# ws2812-hat.net
KiCad netlist of a schematic drawn in EAGLE
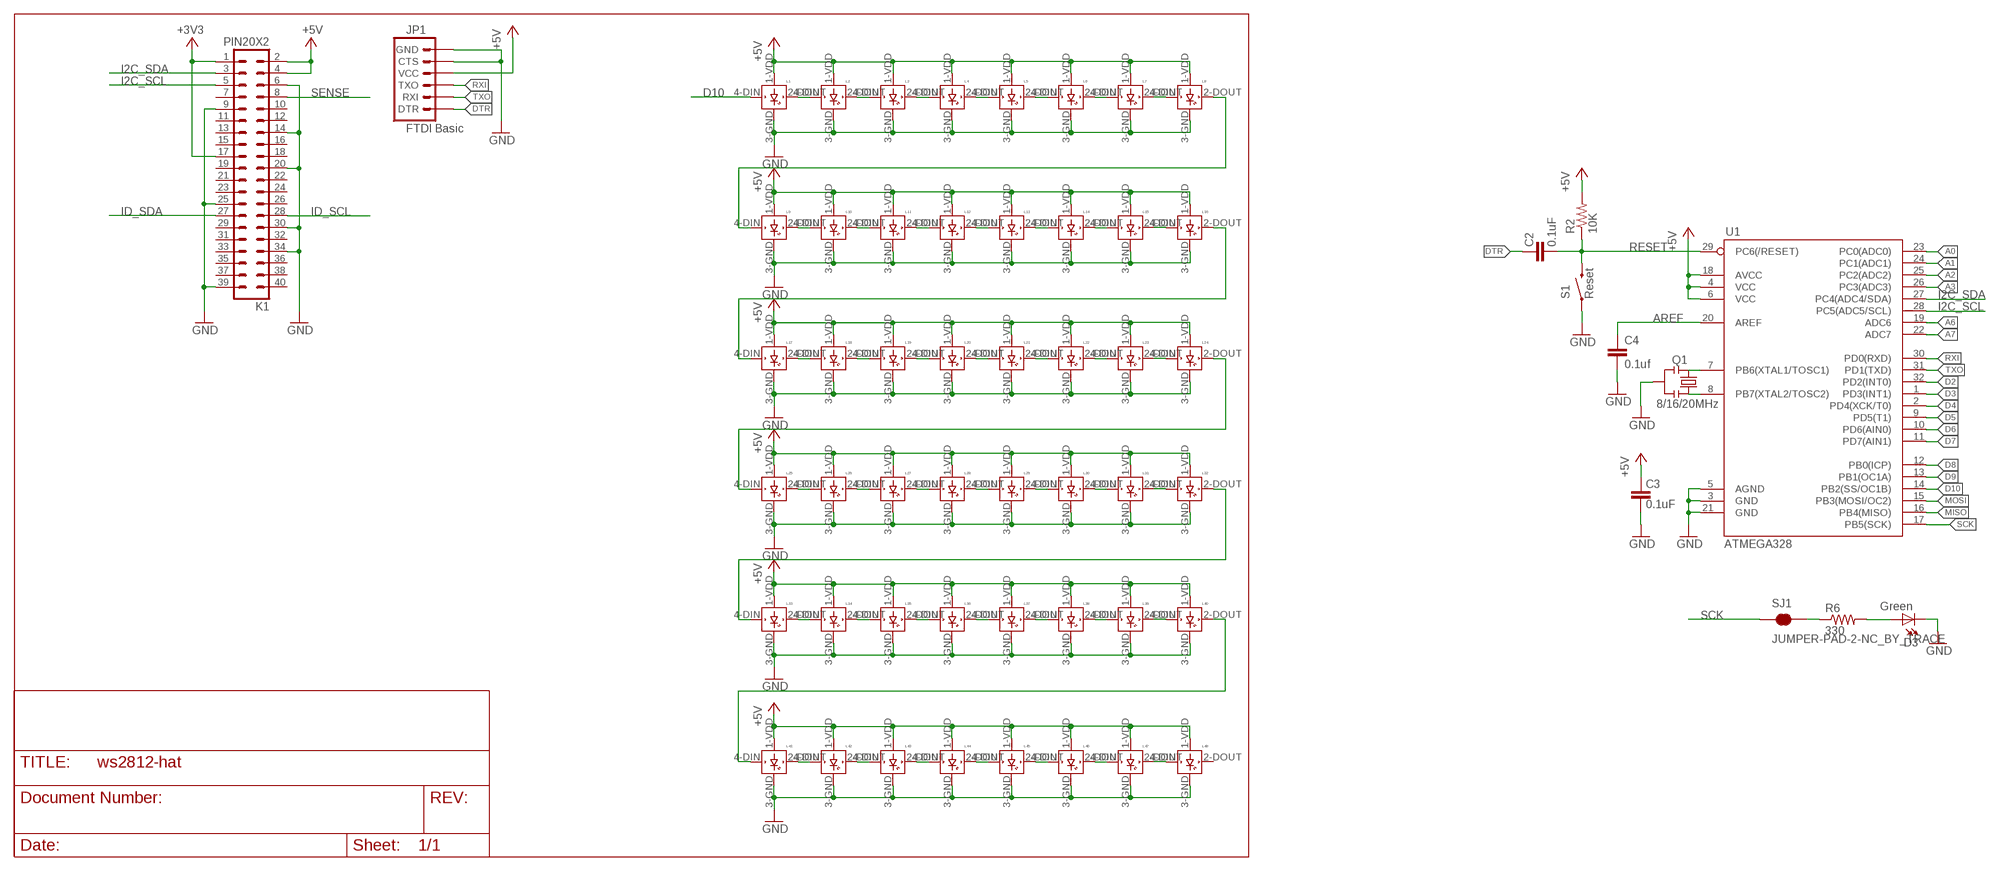
[diagram p0: schematic, sheet 1]

(export (version "E")
  (design (tool "Eeschema 10.0.6"))
  (components
    (comp (ref "C2")
      (value "0.1uF")
      (footprint "eagle-import:0603-CAP")
      (libsource (lib "eagle-import") (part "CAP0603-CAP"))
    )
    (comp (ref "C3")
      (value "0.1uF")
      (footprint "eagle-import:0603-CAP")
      (libsource (lib "eagle-import") (part "CAP0603-CAP"))
    )
    (comp (ref "C4")
      (value "0.1uf")
      (footprint "eagle-import:C0805K")
      (libsource (lib "eagle-import") (part "C-EUC0805K"))
    )
    (comp (ref "D3")
      (value "Green")
      (footprint "eagle-import:0603-LED-ALT1")
      (libsource (lib "eagle-import") (part "LED"))
    )
    (comp (ref "JP1")
      (value "FTDI Basic")
      (footprint "eagle-import:1X06")
      (libsource (lib "eagle-import") (part "ARDUINO_SERIAL_PROGRAMPTH"))
    )
    (comp (ref "K1")
      (value "PIN20X2")
      (footprint "eagle-import:PIN_20X2")
      (libsource (lib "eagle-import") (part "PIN20X2"))
    )
    (comp (ref "L1")
      (value "WS2812B")
      (footprint "eagle-import:WS2812B")
      (libsource (lib "eagle-import") (part "WS2812B"))
    )
    (comp (ref "L2")
      (value "WS2812B")
      (footprint "eagle-import:WS2812B")
      (libsource (lib "eagle-import") (part "WS2812B"))
    )
    (comp (ref "L3")
      (value "WS2812B")
      (footprint "eagle-import:WS2812B")
      (libsource (lib "eagle-import") (part "WS2812B"))
    )
    (comp (ref "L4")
      (value "WS2812B")
      (footprint "eagle-import:WS2812B")
      (libsource (lib "eagle-import") (part "WS2812B"))
    )
    (comp (ref "L5")
      (value "WS2812B")
      (footprint "eagle-import:WS2812B")
      (libsource (lib "eagle-import") (part "WS2812B"))
    )
    (comp (ref "L6")
      (value "WS2812B")
      (footprint "eagle-import:WS2812B")
      (libsource (lib "eagle-import") (part "WS2812B"))
    )
    (comp (ref "L7")
      (value "WS2812B")
      (footprint "eagle-import:WS2812B")
      (libsource (lib "eagle-import") (part "WS2812B"))
    )
    (comp (ref "L8")
      (value "WS2812B")
      (footprint "eagle-import:WS2812B")
      (libsource (lib "eagle-import") (part "WS2812B"))
    )
    (comp (ref "L9")
      (value "WS2812B")
      (footprint "eagle-import:WS2812B")
      (libsource (lib "eagle-import") (part "WS2812B"))
    )
    (comp (ref "L10")
      (value "WS2812B")
      (footprint "eagle-import:WS2812B")
      (libsource (lib "eagle-import") (part "WS2812B"))
    )
    (comp (ref "L11")
      (value "WS2812B")
      (footprint "eagle-import:WS2812B")
      (libsource (lib "eagle-import") (part "WS2812B"))
    )
    (comp (ref "L12")
      (value "WS2812B")
      (footprint "eagle-import:WS2812B")
      (libsource (lib "eagle-import") (part "WS2812B"))
    )
    (comp (ref "L13")
      (value "WS2812B")
      (footprint "eagle-import:WS2812B")
      (libsource (lib "eagle-import") (part "WS2812B"))
    )
    (comp (ref "L14")
      (value "WS2812B")
      (footprint "eagle-import:WS2812B")
      (libsource (lib "eagle-import") (part "WS2812B"))
    )
    (comp (ref "L15")
      (value "WS2812B")
      (footprint "eagle-import:WS2812B")
      (libsource (lib "eagle-import") (part "WS2812B"))
    )
    (comp (ref "L16")
      (value "WS2812B")
      (footprint "eagle-import:WS2812B")
      (libsource (lib "eagle-import") (part "WS2812B"))
    )
    (comp (ref "L17")
      (value "WS2812B")
      (footprint "eagle-import:WS2812B")
      (libsource (lib "eagle-import") (part "WS2812B"))
    )
    (comp (ref "L18")
      (value "WS2812B")
      (footprint "eagle-import:WS2812B")
      (libsource (lib "eagle-import") (part "WS2812B"))
    )
    (comp (ref "L19")
      (value "WS2812B")
      (footprint "eagle-import:WS2812B")
      (libsource (lib "eagle-import") (part "WS2812B"))
    )
    (comp (ref "L20")
      (value "WS2812B")
      (footprint "eagle-import:WS2812B")
      (libsource (lib "eagle-import") (part "WS2812B"))
    )
    (comp (ref "L21")
      (value "WS2812B")
      (footprint "eagle-import:WS2812B")
      (libsource (lib "eagle-import") (part "WS2812B"))
    )
    (comp (ref "L22")
      (value "WS2812B")
      (footprint "eagle-import:WS2812B")
      (libsource (lib "eagle-import") (part "WS2812B"))
    )
    (comp (ref "L23")
      (value "WS2812B")
      (footprint "eagle-import:WS2812B")
      (libsource (lib "eagle-import") (part "WS2812B"))
    )
    (comp (ref "L24")
      (value "WS2812B")
      (footprint "eagle-import:WS2812B")
      (libsource (lib "eagle-import") (part "WS2812B"))
    )
    (comp (ref "L25")
      (value "WS2812B")
      (footprint "eagle-import:WS2812B")
      (libsource (lib "eagle-import") (part "WS2812B"))
    )
    (comp (ref "L26")
      (value "WS2812B")
      (footprint "eagle-import:WS2812B")
      (libsource (lib "eagle-import") (part "WS2812B"))
    )
    (comp (ref "L27")
      (value "WS2812B")
      (footprint "eagle-import:WS2812B")
      (libsource (lib "eagle-import") (part "WS2812B"))
    )
    (comp (ref "L28")
      (value "WS2812B")
      (footprint "eagle-import:WS2812B")
      (libsource (lib "eagle-import") (part "WS2812B"))
    )
    (comp (ref "L29")
      (value "WS2812B")
      (footprint "eagle-import:WS2812B")
      (libsource (lib "eagle-import") (part "WS2812B"))
    )
    (comp (ref "L30")
      (value "WS2812B")
      (footprint "eagle-import:WS2812B")
      (libsource (lib "eagle-import") (part "WS2812B"))
    )
    (comp (ref "L31")
      (value "WS2812B")
      (footprint "eagle-import:WS2812B")
      (libsource (lib "eagle-import") (part "WS2812B"))
    )
    (comp (ref "L32")
      (value "WS2812B")
      (footprint "eagle-import:WS2812B")
      (libsource (lib "eagle-import") (part "WS2812B"))
    )
    (comp (ref "L33")
      (value "WS2812B")
      (footprint "eagle-import:WS2812B")
      (libsource (lib "eagle-import") (part "WS2812B"))
    )
    (comp (ref "L34")
      (value "WS2812B")
      (footprint "eagle-import:WS2812B")
      (libsource (lib "eagle-import") (part "WS2812B"))
    )
    (comp (ref "L35")
      (value "WS2812B")
      (footprint "eagle-import:WS2812B")
      (libsource (lib "eagle-import") (part "WS2812B"))
    )
    (comp (ref "L36")
      (value "WS2812B")
      (footprint "eagle-import:WS2812B")
      (libsource (lib "eagle-import") (part "WS2812B"))
    )
    (comp (ref "L37")
      (value "WS2812B")
      (footprint "eagle-import:WS2812B")
      (libsource (lib "eagle-import") (part "WS2812B"))
    )
    (comp (ref "L38")
      (value "WS2812B")
      (footprint "eagle-import:WS2812B")
      (libsource (lib "eagle-import") (part "WS2812B"))
    )
    (comp (ref "L39")
      (value "WS2812B")
      (footprint "eagle-import:WS2812B")
      (libsource (lib "eagle-import") (part "WS2812B"))
    )
    (comp (ref "L40")
      (value "WS2812B")
      (footprint "eagle-import:WS2812B")
      (libsource (lib "eagle-import") (part "WS2812B"))
    )
    (comp (ref "L41")
      (value "WS2812B")
      (footprint "eagle-import:WS2812B")
      (libsource (lib "eagle-import") (part "WS2812B"))
    )
    (comp (ref "L42")
      (value "WS2812B")
      (footprint "eagle-import:WS2812B")
      (libsource (lib "eagle-import") (part "WS2812B"))
    )
    (comp (ref "L43")
      (value "WS2812B")
      (footprint "eagle-import:WS2812B")
      (libsource (lib "eagle-import") (part "WS2812B"))
    )
    (comp (ref "L44")
      (value "WS2812B")
      (footprint "eagle-import:WS2812B")
      (libsource (lib "eagle-import") (part "WS2812B"))
    )
    (comp (ref "L45")
      (value "WS2812B")
      (footprint "eagle-import:WS2812B")
      (libsource (lib "eagle-import") (part "WS2812B"))
    )
    (comp (ref "L46")
      (value "WS2812B")
      (footprint "eagle-import:WS2812B")
      (libsource (lib "eagle-import") (part "WS2812B"))
    )
    (comp (ref "L47")
      (value "WS2812B")
      (footprint "eagle-import:WS2812B")
      (libsource (lib "eagle-import") (part "WS2812B"))
    )
    (comp (ref "L48")
      (value "WS2812B")
      (footprint "eagle-import:WS2812B")
      (libsource (lib "eagle-import") (part "WS2812B"))
    )
    (comp (ref "Q1")
      (value "8/16/20MHz")
      (footprint "eagle-import:RESONATOR-SMD-1_1")
      (libsource (lib "eagle-import") (part "RESONATOR1{colon}1"))
    )
    (comp (ref "R2")
      (value "10K")
      (footprint "eagle-import:0603-RES")
      (libsource (lib "eagle-import") (part "RESISTOR0603-RES"))
    )
    (comp (ref "R6")
      (value "330")
      (footprint "eagle-import:0603-RES")
      (libsource (lib "eagle-import") (part "RESISTOR0603-RES"))
    )
    (comp (ref "S1")
      (value "Reset")
      (footprint "eagle-import:TACTILE-SWITCH-SMD-ALT01")
      (libsource (lib "eagle-import") (part "SWITCH-MOMENTARY-2SMD-ALT01"))
    )
    (comp (ref "SJ1")
      (value "JUMPER-PAD-2-NC_BY_TRACE")
      (footprint "eagle-import:PAD-JUMPER-2-NC_BY_TRACE_YES_SILK")
      (libsource (lib "eagle-import") (part "JUMPER-PAD-2-NC_BY_TRACE"))
    )
    (comp (ref "U1")
      (value "ATMEGA328")
      (footprint "eagle-import:TQFP32-08")
      (libsource (lib "eagle-import") (part "ATMEGA168"))
    )
  )
  (nets
    (net (code "1") (name "+3V3") (class "Default")
      (node (ref "K1") (pin "1") (pinfunction "1_1") (pintype "passive"))
      (node (ref "K1") (pin "17") (pinfunction "17_17") (pintype "passive"))
    )
    (net (code "2") (name "+5V") (class "Default")
      (node (ref "C3") (pin "2") (pinfunction "2_2") (pintype "passive"))
      (node (ref "JP1") (pin "4") (pinfunction "VCC_4") (pintype "passive"))
      (node (ref "K1") (pin "2") (pinfunction "2_2") (pintype "passive"))
      (node (ref "K1") (pin "4") (pinfunction "4_4") (pintype "passive"))
      (node (ref "L1") (pin "1-VDD") (pinfunction "VDD_1-VDD") (pintype "bidirectional"))
      (node (ref "L10") (pin "1-VDD") (pinfunction "VDD_1-VDD") (pintype "bidirectional"))
      (node (ref "L11") (pin "1-VDD") (pinfunction "VDD_1-VDD") (pintype "bidirectional"))
      (node (ref "L12") (pin "1-VDD") (pinfunction "VDD_1-VDD") (pintype "bidirectional"))
      (node (ref "L13") (pin "1-VDD") (pinfunction "VDD_1-VDD") (pintype "bidirectional"))
      (node (ref "L14") (pin "1-VDD") (pinfunction "VDD_1-VDD") (pintype "bidirectional"))
      (node (ref "L15") (pin "1-VDD") (pinfunction "VDD_1-VDD") (pintype "bidirectional"))
      (node (ref "L16") (pin "1-VDD") (pinfunction "VDD_1-VDD") (pintype "bidirectional"))
      (node (ref "L17") (pin "1-VDD") (pinfunction "VDD_1-VDD") (pintype "bidirectional"))
      (node (ref "L18") (pin "1-VDD") (pinfunction "VDD_1-VDD") (pintype "bidirectional"))
      (node (ref "L19") (pin "1-VDD") (pinfunction "VDD_1-VDD") (pintype "bidirectional"))
      (node (ref "L2") (pin "1-VDD") (pinfunction "VDD_1-VDD") (pintype "bidirectional"))
      (node (ref "L20") (pin "1-VDD") (pinfunction "VDD_1-VDD") (pintype "bidirectional"))
      (node (ref "L21") (pin "1-VDD") (pinfunction "VDD_1-VDD") (pintype "bidirectional"))
      (node (ref "L22") (pin "1-VDD") (pinfunction "VDD_1-VDD") (pintype "bidirectional"))
      (node (ref "L23") (pin "1-VDD") (pinfunction "VDD_1-VDD") (pintype "bidirectional"))
      (node (ref "L24") (pin "1-VDD") (pinfunction "VDD_1-VDD") (pintype "bidirectional"))
      (node (ref "L25") (pin "1-VDD") (pinfunction "VDD_1-VDD") (pintype "bidirectional"))
      (node (ref "L26") (pin "1-VDD") (pinfunction "VDD_1-VDD") (pintype "bidirectional"))
      (node (ref "L27") (pin "1-VDD") (pinfunction "VDD_1-VDD") (pintype "bidirectional"))
      (node (ref "L28") (pin "1-VDD") (pinfunction "VDD_1-VDD") (pintype "bidirectional"))
      (node (ref "L29") (pin "1-VDD") (pinfunction "VDD_1-VDD") (pintype "bidirectional"))
      (node (ref "L3") (pin "1-VDD") (pinfunction "VDD_1-VDD") (pintype "bidirectional"))
      (node (ref "L30") (pin "1-VDD") (pinfunction "VDD_1-VDD") (pintype "bidirectional"))
      (node (ref "L31") (pin "1-VDD") (pinfunction "VDD_1-VDD") (pintype "bidirectional"))
      (node (ref "L32") (pin "1-VDD") (pinfunction "VDD_1-VDD") (pintype "bidirectional"))
      (node (ref "L33") (pin "1-VDD") (pinfunction "VDD_1-VDD") (pintype "bidirectional"))
      (node (ref "L34") (pin "1-VDD") (pinfunction "VDD_1-VDD") (pintype "bidirectional"))
      (node (ref "L35") (pin "1-VDD") (pinfunction "VDD_1-VDD") (pintype "bidirectional"))
      (node (ref "L36") (pin "1-VDD") (pinfunction "VDD_1-VDD") (pintype "bidirectional"))
      (node (ref "L37") (pin "1-VDD") (pinfunction "VDD_1-VDD") (pintype "bidirectional"))
      (node (ref "L38") (pin "1-VDD") (pinfunction "VDD_1-VDD") (pintype "bidirectional"))
      (node (ref "L39") (pin "1-VDD") (pinfunction "VDD_1-VDD") (pintype "bidirectional"))
      (node (ref "L4") (pin "1-VDD") (pinfunction "VDD_1-VDD") (pintype "bidirectional"))
      (node (ref "L40") (pin "1-VDD") (pinfunction "VDD_1-VDD") (pintype "bidirectional"))
      (node (ref "L41") (pin "1-VDD") (pinfunction "VDD_1-VDD") (pintype "bidirectional"))
      (node (ref "L42") (pin "1-VDD") (pinfunction "VDD_1-VDD") (pintype "bidirectional"))
      (node (ref "L43") (pin "1-VDD") (pinfunction "VDD_1-VDD") (pintype "bidirectional"))
      (node (ref "L44") (pin "1-VDD") (pinfunction "VDD_1-VDD") (pintype "bidirectional"))
      (node (ref "L45") (pin "1-VDD") (pinfunction "VDD_1-VDD") (pintype "bidirectional"))
      (node (ref "L46") (pin "1-VDD") (pinfunction "VDD_1-VDD") (pintype "bidirectional"))
      (node (ref "L47") (pin "1-VDD") (pinfunction "VDD_1-VDD") (pintype "bidirectional"))
      (node (ref "L48") (pin "1-VDD") (pinfunction "VDD_1-VDD") (pintype "bidirectional"))
      (node (ref "L5") (pin "1-VDD") (pinfunction "VDD_1-VDD") (pintype "bidirectional"))
      (node (ref "L6") (pin "1-VDD") (pinfunction "VDD_1-VDD") (pintype "bidirectional"))
      (node (ref "L7") (pin "1-VDD") (pinfunction "VDD_1-VDD") (pintype "bidirectional"))
      (node (ref "L8") (pin "1-VDD") (pinfunction "VDD_1-VDD") (pintype "bidirectional"))
      (node (ref "L9") (pin "1-VDD") (pinfunction "VDD_1-VDD") (pintype "bidirectional"))
      (node (ref "R2") (pin "2") (pinfunction "2_2") (pintype "passive"))
      (node (ref "U1") (pin "18") (pinfunction "AVCC_18") (pintype "bidirectional"))
      (node (ref "U1") (pin "4") (pinfunction "VCC_4") (pintype "bidirectional"))
      (node (ref "U1") (pin "6") (pinfunction "VCC_6") (pintype "bidirectional"))
    )
    (net (code "3") (name "/AREF") (class "Default")
      (node (ref "C4") (pin "1") (pinfunction "1_1") (pintype "passive"))
      (node (ref "U1") (pin "20") (pinfunction "AREF_20") (pintype "bidirectional"))
    )
    (net (code "4") (name "/I2C_SCL") (class "Default")
      (node (ref "K1") (pin "5") (pinfunction "5_5") (pintype "passive"))
      (node (ref "U1") (pin "28") (pinfunction "PC5(ADC5/SCL)_28") (pintype "bidirectional"))
    )
    (net (code "5") (name "/I2C_SDA") (class "Default")
      (node (ref "K1") (pin "3") (pinfunction "3_3") (pintype "passive"))
      (node (ref "U1") (pin "27") (pinfunction "PC4(ADC4/SDA)_27") (pintype "bidirectional"))
    )
    (net (code "6") (name "/ID_SCL") (class "Default")
      (node (ref "K1") (pin "28") (pinfunction "28_28") (pintype "passive"))
    )
    (net (code "7") (name "/ID_SDA") (class "Default")
      (node (ref "K1") (pin "27") (pinfunction "27_27") (pintype "passive"))
    )
    (net (code "8") (name "/RESET") (class "Default")
      (node (ref "C2") (pin "1") (pinfunction "1_1") (pintype "passive"))
      (node (ref "R2") (pin "1") (pinfunction "1_1") (pintype "passive"))
      (node (ref "S1") (pin "3") (pinfunction "2_3") (pintype "passive"))
      (node (ref "S1") (pin "4") (pinfunction "2_4") (pintype "passive"))
      (node (ref "U1") (pin "29") (pinfunction "PC6(/RESET)_29") (pintype "bidirectional"))
    )
    (net (code "9") (name "/SENSE") (class "Default")
      (node (ref "K1") (pin "8") (pinfunction "8_8") (pintype "passive"))
    )
    (net (code "10") (name "A0") (class "Default")
      (node (ref "U1") (pin "23") (pinfunction "PC0(ADC0)_23") (pintype "bidirectional"))
    )
    (net (code "11") (name "A1") (class "Default")
      (node (ref "U1") (pin "24") (pinfunction "PC1(ADC1)_24") (pintype "bidirectional"))
    )
    (net (code "12") (name "A2") (class "Default")
      (node (ref "U1") (pin "25") (pinfunction "PC2(ADC2)_25") (pintype "bidirectional"))
    )
    (net (code "13") (name "A3") (class "Default")
      (node (ref "U1") (pin "26") (pinfunction "PC3(ADC3)_26") (pintype "bidirectional"))
    )
    (net (code "14") (name "A6") (class "Default")
      (node (ref "U1") (pin "19") (pinfunction "ADC6_19") (pintype "bidirectional"))
    )
    (net (code "15") (name "A7") (class "Default")
      (node (ref "U1") (pin "22") (pinfunction "ADC7_22") (pintype "bidirectional"))
    )
    (net (code "16") (name "D2") (class "Default")
      (node (ref "U1") (pin "32") (pinfunction "PD2(INT0)_32") (pintype "bidirectional"))
    )
    (net (code "17") (name "D3") (class "Default")
      (node (ref "U1") (pin "1") (pinfunction "PD3(INT1)_1") (pintype "bidirectional"))
    )
    (net (code "18") (name "D4") (class "Default")
      (node (ref "U1") (pin "2") (pinfunction "PD4(XCK/T0)_2") (pintype "bidirectional"))
    )
    (net (code "19") (name "D5") (class "Default")
      (node (ref "U1") (pin "9") (pinfunction "PD5(T1)_9") (pintype "bidirectional"))
    )
    (net (code "20") (name "D6") (class "Default")
      (node (ref "U1") (pin "10") (pinfunction "PD6(AIN0)_10") (pintype "bidirectional"))
    )
    (net (code "21") (name "D7") (class "Default")
      (node (ref "U1") (pin "11") (pinfunction "PD7(AIN1)_11") (pintype "bidirectional"))
    )
    (net (code "22") (name "D8") (class "Default")
      (node (ref "U1") (pin "12") (pinfunction "PB0(ICP)_12") (pintype "bidirectional"))
    )
    (net (code "23") (name "D9") (class "Default")
      (node (ref "U1") (pin "13") (pinfunction "PB1(OC1A)_13") (pintype "bidirectional"))
    )
    (net (code "24") (name "D10") (class "Default")
      (node (ref "L1") (pin "4-DIN") (pinfunction "DIN_4-DIN") (pintype "input"))
      (node (ref "U1") (pin "14") (pinfunction "PB2(SS/OC1B)_14") (pintype "bidirectional"))
    )
    (net (code "25") (name "DTR") (class "Default")
      (node (ref "C2") (pin "2") (pinfunction "2_2") (pintype "passive"))
      (node (ref "JP1") (pin "1") (pinfunction "DTR_1") (pintype "passive"))
    )
    (net (code "26") (name "GND") (class "Default")
      (node (ref "C3") (pin "1") (pinfunction "1_1") (pintype "passive"))
      (node (ref "C4") (pin "2") (pinfunction "2_2") (pintype "passive"))
      (node (ref "D3") (pin "C") (pinfunction "C_C") (pintype "passive"))
      (node (ref "JP1") (pin "5") (pinfunction "CTS_5") (pintype "passive"))
      (node (ref "JP1") (pin "6") (pinfunction "GND_6") (pintype "passive"))
      (node (ref "K1") (pin "14") (pinfunction "14_14") (pintype "passive"))
      (node (ref "K1") (pin "20") (pinfunction "20_20") (pintype "passive"))
      (node (ref "K1") (pin "25") (pinfunction "25_25") (pintype "passive"))
      (node (ref "K1") (pin "30") (pinfunction "30_30") (pintype "passive"))
      (node (ref "K1") (pin "34") (pinfunction "34_34") (pintype "passive"))
      (node (ref "K1") (pin "39") (pinfunction "39_39") (pintype "passive"))
      (node (ref "K1") (pin "6") (pinfunction "6_6") (pintype "passive"))
      (node (ref "K1") (pin "9") (pinfunction "9_9") (pintype "passive"))
      (node (ref "L1") (pin "3-GND") (pinfunction "GND_3-GND") (pintype "bidirectional"))
      (node (ref "L10") (pin "3-GND") (pinfunction "GND_3-GND") (pintype "bidirectional"))
      (node (ref "L11") (pin "3-GND") (pinfunction "GND_3-GND") (pintype "bidirectional"))
      (node (ref "L12") (pin "3-GND") (pinfunction "GND_3-GND") (pintype "bidirectional"))
      (node (ref "L13") (pin "3-GND") (pinfunction "GND_3-GND") (pintype "bidirectional"))
      (node (ref "L14") (pin "3-GND") (pinfunction "GND_3-GND") (pintype "bidirectional"))
      (node (ref "L15") (pin "3-GND") (pinfunction "GND_3-GND") (pintype "bidirectional"))
      (node (ref "L16") (pin "3-GND") (pinfunction "GND_3-GND") (pintype "bidirectional"))
      (node (ref "L17") (pin "3-GND") (pinfunction "GND_3-GND") (pintype "bidirectional"))
      (node (ref "L18") (pin "3-GND") (pinfunction "GND_3-GND") (pintype "bidirectional"))
      (node (ref "L19") (pin "3-GND") (pinfunction "GND_3-GND") (pintype "bidirectional"))
      (node (ref "L2") (pin "3-GND") (pinfunction "GND_3-GND") (pintype "bidirectional"))
      (node (ref "L20") (pin "3-GND") (pinfunction "GND_3-GND") (pintype "bidirectional"))
      (node (ref "L21") (pin "3-GND") (pinfunction "GND_3-GND") (pintype "bidirectional"))
      (node (ref "L22") (pin "3-GND") (pinfunction "GND_3-GND") (pintype "bidirectional"))
      (node (ref "L23") (pin "3-GND") (pinfunction "GND_3-GND") (pintype "bidirectional"))
      (node (ref "L24") (pin "3-GND") (pinfunction "GND_3-GND") (pintype "bidirectional"))
      (node (ref "L25") (pin "3-GND") (pinfunction "GND_3-GND") (pintype "bidirectional"))
      (node (ref "L26") (pin "3-GND") (pinfunction "GND_3-GND") (pintype "bidirectional"))
      (node (ref "L27") (pin "3-GND") (pinfunction "GND_3-GND") (pintype "bidirectional"))
      (node (ref "L28") (pin "3-GND") (pinfunction "GND_3-GND") (pintype "bidirectional"))
      (node (ref "L29") (pin "3-GND") (pinfunction "GND_3-GND") (pintype "bidirectional"))
      (node (ref "L3") (pin "3-GND") (pinfunction "GND_3-GND") (pintype "bidirectional"))
      (node (ref "L30") (pin "3-GND") (pinfunction "GND_3-GND") (pintype "bidirectional"))
      (node (ref "L31") (pin "3-GND") (pinfunction "GND_3-GND") (pintype "bidirectional"))
      (node (ref "L32") (pin "3-GND") (pinfunction "GND_3-GND") (pintype "bidirectional"))
      (node (ref "L33") (pin "3-GND") (pinfunction "GND_3-GND") (pintype "bidirectional"))
      (node (ref "L34") (pin "3-GND") (pinfunction "GND_3-GND") (pintype "bidirectional"))
      (node (ref "L35") (pin "3-GND") (pinfunction "GND_3-GND") (pintype "bidirectional"))
      (node (ref "L36") (pin "3-GND") (pinfunction "GND_3-GND") (pintype "bidirectional"))
      (node (ref "L37") (pin "3-GND") (pinfunction "GND_3-GND") (pintype "bidirectional"))
      (node (ref "L38") (pin "3-GND") (pinfunction "GND_3-GND") (pintype "bidirectional"))
      (node (ref "L39") (pin "3-GND") (pinfunction "GND_3-GND") (pintype "bidirectional"))
      (node (ref "L4") (pin "3-GND") (pinfunction "GND_3-GND") (pintype "bidirectional"))
      (node (ref "L40") (pin "3-GND") (pinfunction "GND_3-GND") (pintype "bidirectional"))
      (node (ref "L41") (pin "3-GND") (pinfunction "GND_3-GND") (pintype "bidirectional"))
      (node (ref "L42") (pin "3-GND") (pinfunction "GND_3-GND") (pintype "bidirectional"))
      (node (ref "L43") (pin "3-GND") (pinfunction "GND_3-GND") (pintype "bidirectional"))
      (node (ref "L44") (pin "3-GND") (pinfunction "GND_3-GND") (pintype "bidirectional"))
      (node (ref "L45") (pin "3-GND") (pinfunction "GND_3-GND") (pintype "bidirectional"))
      (node (ref "L46") (pin "3-GND") (pinfunction "GND_3-GND") (pintype "bidirectional"))
      (node (ref "L47") (pin "3-GND") (pinfunction "GND_3-GND") (pintype "bidirectional"))
      (node (ref "L48") (pin "3-GND") (pinfunction "GND_3-GND") (pintype "bidirectional"))
      (node (ref "L5") (pin "3-GND") (pinfunction "GND_3-GND") (pintype "bidirectional"))
      (node (ref "L6") (pin "3-GND") (pinfunction "GND_3-GND") (pintype "bidirectional"))
      (node (ref "L7") (pin "3-GND") (pinfunction "GND_3-GND") (pintype "bidirectional"))
      (node (ref "L8") (pin "3-GND") (pinfunction "GND_3-GND") (pintype "bidirectional"))
      (node (ref "L9") (pin "3-GND") (pinfunction "GND_3-GND") (pintype "bidirectional"))
      (node (ref "Q1") (pin "2") (pinfunction "2_2") (pintype "passive"))
      (node (ref "S1") (pin "1") (pinfunction "1_1") (pintype "passive"))
      (node (ref "S1") (pin "2") (pinfunction "1_2") (pintype "passive"))
      (node (ref "U1") (pin "21") (pinfunction "GND_21") (pintype "bidirectional"))
      (node (ref "U1") (pin "3") (pinfunction "GND_3") (pintype "bidirectional"))
      (node (ref "U1") (pin "5") (pinfunction "AGND_5") (pintype "bidirectional"))
    )
    (net (code "27") (name "MISO") (class "Default")
      (node (ref "U1") (pin "16") (pinfunction "PB4(MISO)_16") (pintype "bidirectional"))
    )
    (net (code "28") (name "MOSI") (class "Default")
      (node (ref "U1") (pin "15") (pinfunction "PB3(MOSI/OC2)_15") (pintype "bidirectional"))
    )
    (net (code "29") (name "Net-(D3-PadA)") (class "Default")
      (node (ref "D3") (pin "A") (pinfunction "A_A") (pintype "passive"))
      (node (ref "R6") (pin "2") (pinfunction "2_2") (pintype "passive"))
    )
    (net (code "30") (name "Net-(L1-DOUT)") (class "Default")
      (node (ref "L1") (pin "2-DOUT") (pinfunction "DOUT_2-DOUT") (pintype "output"))
      (node (ref "L2") (pin "4-DIN") (pinfunction "DIN_4-DIN") (pintype "input"))
    )
    (net (code "31") (name "Net-(L2-DOUT)") (class "Default")
      (node (ref "L2") (pin "2-DOUT") (pinfunction "DOUT_2-DOUT") (pintype "output"))
      (node (ref "L3") (pin "4-DIN") (pinfunction "DIN_4-DIN") (pintype "input"))
    )
    (net (code "32") (name "Net-(L3-DOUT)") (class "Default")
      (node (ref "L3") (pin "2-DOUT") (pinfunction "DOUT_2-DOUT") (pintype "output"))
      (node (ref "L4") (pin "4-DIN") (pinfunction "DIN_4-DIN") (pintype "input"))
    )
    (net (code "33") (name "Net-(L4-DOUT)") (class "Default")
      (node (ref "L4") (pin "2-DOUT") (pinfunction "DOUT_2-DOUT") (pintype "output"))
      (node (ref "L5") (pin "4-DIN") (pinfunction "DIN_4-DIN") (pintype "input"))
    )
    (net (code "34") (name "Net-(L5-DOUT)") (class "Default")
      (node (ref "L5") (pin "2-DOUT") (pinfunction "DOUT_2-DOUT") (pintype "output"))
      (node (ref "L6") (pin "4-DIN") (pinfunction "DIN_4-DIN") (pintype "input"))
    )
    (net (code "35") (name "Net-(L6-DOUT)") (class "Default")
      (node (ref "L6") (pin "2-DOUT") (pinfunction "DOUT_2-DOUT") (pintype "output"))
      (node (ref "L7") (pin "4-DIN") (pinfunction "DIN_4-DIN") (pintype "input"))
    )
    (net (code "36") (name "Net-(L7-DOUT)") (class "Default")
      (node (ref "L7") (pin "2-DOUT") (pinfunction "DOUT_2-DOUT") (pintype "output"))
      (node (ref "L8") (pin "4-DIN") (pinfunction "DIN_4-DIN") (pintype "input"))
    )
    (net (code "37") (name "Net-(L8-DOUT)") (class "Default")
      (node (ref "L8") (pin "2-DOUT") (pinfunction "DOUT_2-DOUT") (pintype "output"))
      (node (ref "L9") (pin "4-DIN") (pinfunction "DIN_4-DIN") (pintype "input"))
    )
    (net (code "38") (name "Net-(L10-DIN)") (class "Default")
      (node (ref "L10") (pin "4-DIN") (pinfunction "DIN_4-DIN") (pintype "input"))
      (node (ref "L9") (pin "2-DOUT") (pinfunction "DOUT_2-DOUT") (pintype "output"))
    )
    (net (code "39") (name "Net-(L10-DOUT)") (class "Default")
      (node (ref "L10") (pin "2-DOUT") (pinfunction "DOUT_2-DOUT") (pintype "output"))
      (node (ref "L11") (pin "4-DIN") (pinfunction "DIN_4-DIN") (pintype "input"))
    )
    (net (code "40") (name "Net-(L11-DOUT)") (class "Default")
      (node (ref "L11") (pin "2-DOUT") (pinfunction "DOUT_2-DOUT") (pintype "output"))
      (node (ref "L12") (pin "4-DIN") (pinfunction "DIN_4-DIN") (pintype "input"))
    )
    (net (code "41") (name "Net-(L12-DOUT)") (class "Default")
      (node (ref "L12") (pin "2-DOUT") (pinfunction "DOUT_2-DOUT") (pintype "output"))
      (node (ref "L13") (pin "4-DIN") (pinfunction "DIN_4-DIN") (pintype "input"))
    )
    (net (code "42") (name "Net-(L13-DOUT)") (class "Default")
      (node (ref "L13") (pin "2-DOUT") (pinfunction "DOUT_2-DOUT") (pintype "output"))
      (node (ref "L14") (pin "4-DIN") (pinfunction "DIN_4-DIN") (pintype "input"))
    )
    (net (code "43") (name "Net-(L14-DOUT)") (class "Default")
      (node (ref "L14") (pin "2-DOUT") (pinfunction "DOUT_2-DOUT") (pintype "output"))
      (node (ref "L15") (pin "4-DIN") (pinfunction "DIN_4-DIN") (pintype "input"))
    )
    (net (code "44") (name "Net-(L15-DOUT)") (class "Default")
      (node (ref "L15") (pin "2-DOUT") (pinfunction "DOUT_2-DOUT") (pintype "output"))
      (node (ref "L16") (pin "4-DIN") (pinfunction "DIN_4-DIN") (pintype "input"))
    )
    (net (code "45") (name "Net-(L16-DOUT)") (class "Default")
      (node (ref "L16") (pin "2-DOUT") (pinfunction "DOUT_2-DOUT") (pintype "output"))
      (node (ref "L17") (pin "4-DIN") (pinfunction "DIN_4-DIN") (pintype "input"))
    )
    (net (code "46") (name "Net-(L17-DOUT)") (class "Default")
      (node (ref "L17") (pin "2-DOUT") (pinfunction "DOUT_2-DOUT") (pintype "output"))
      (node (ref "L18") (pin "4-DIN") (pinfunction "DIN_4-DIN") (pintype "input"))
    )
    (net (code "47") (name "Net-(L18-DOUT)") (class "Default")
      (node (ref "L18") (pin "2-DOUT") (pinfunction "DOUT_2-DOUT") (pintype "output"))
      (node (ref "L19") (pin "4-DIN") (pinfunction "DIN_4-DIN") (pintype "input"))
    )
    (net (code "48") (name "Net-(L19-DOUT)") (class "Default")
      (node (ref "L19") (pin "2-DOUT") (pinfunction "DOUT_2-DOUT") (pintype "output"))
      (node (ref "L20") (pin "4-DIN") (pinfunction "DIN_4-DIN") (pintype "input"))
    )
    (net (code "49") (name "Net-(L20-DOUT)") (class "Default")
      (node (ref "L20") (pin "2-DOUT") (pinfunction "DOUT_2-DOUT") (pintype "output"))
      (node (ref "L21") (pin "4-DIN") (pinfunction "DIN_4-DIN") (pintype "input"))
    )
    (net (code "50") (name "Net-(L21-DOUT)") (class "Default")
      (node (ref "L21") (pin "2-DOUT") (pinfunction "DOUT_2-DOUT") (pintype "output"))
      (node (ref "L22") (pin "4-DIN") (pinfunction "DIN_4-DIN") (pintype "input"))
    )
    (net (code "51") (name "Net-(L22-DOUT)") (class "Default")
      (node (ref "L22") (pin "2-DOUT") (pinfunction "DOUT_2-DOUT") (pintype "output"))
      (node (ref "L23") (pin "4-DIN") (pinfunction "DIN_4-DIN") (pintype "input"))
    )
    (net (code "52") (name "Net-(L23-DOUT)") (class "Default")
      (node (ref "L23") (pin "2-DOUT") (pinfunction "DOUT_2-DOUT") (pintype "output"))
      (node (ref "L24") (pin "4-DIN") (pinfunction "DIN_4-DIN") (pintype "input"))
    )
    (net (code "53") (name "Net-(L24-DOUT)") (class "Default")
      (node (ref "L24") (pin "2-DOUT") (pinfunction "DOUT_2-DOUT") (pintype "output"))
      (node (ref "L25") (pin "4-DIN") (pinfunction "DIN_4-DIN") (pintype "input"))
    )
    (net (code "54") (name "Net-(L25-DOUT)") (class "Default")
      (node (ref "L25") (pin "2-DOUT") (pinfunction "DOUT_2-DOUT") (pintype "output"))
      (node (ref "L26") (pin "4-DIN") (pinfunction "DIN_4-DIN") (pintype "input"))
    )
    (net (code "55") (name "Net-(L26-DOUT)") (class "Default")
      (node (ref "L26") (pin "2-DOUT") (pinfunction "DOUT_2-DOUT") (pintype "output"))
      (node (ref "L27") (pin "4-DIN") (pinfunction "DIN_4-DIN") (pintype "input"))
    )
    (net (code "56") (name "Net-(L27-DOUT)") (class "Default")
      (node (ref "L27") (pin "2-DOUT") (pinfunction "DOUT_2-DOUT") (pintype "output"))
      (node (ref "L28") (pin "4-DIN") (pinfunction "DIN_4-DIN") (pintype "input"))
    )
    (net (code "57") (name "Net-(L28-DOUT)") (class "Default")
      (node (ref "L28") (pin "2-DOUT") (pinfunction "DOUT_2-DOUT") (pintype "output"))
      (node (ref "L29") (pin "4-DIN") (pinfunction "DIN_4-DIN") (pintype "input"))
    )
    (net (code "58") (name "Net-(L29-DOUT)") (class "Default")
      (node (ref "L29") (pin "2-DOUT") (pinfunction "DOUT_2-DOUT") (pintype "output"))
      (node (ref "L30") (pin "4-DIN") (pinfunction "DIN_4-DIN") (pintype "input"))
    )
    (net (code "59") (name "Net-(L30-DOUT)") (class "Default")
      (node (ref "L30") (pin "2-DOUT") (pinfunction "DOUT_2-DOUT") (pintype "output"))
      (node (ref "L31") (pin "4-DIN") (pinfunction "DIN_4-DIN") (pintype "input"))
    )
    (net (code "60") (name "Net-(L31-DOUT)") (class "Default")
      (node (ref "L31") (pin "2-DOUT") (pinfunction "DOUT_2-DOUT") (pintype "output"))
      (node (ref "L32") (pin "4-DIN") (pinfunction "DIN_4-DIN") (pintype "input"))
    )
    (net (code "61") (name "Net-(L32-DOUT)") (class "Default")
      (node (ref "L32") (pin "2-DOUT") (pinfunction "DOUT_2-DOUT") (pintype "output"))
      (node (ref "L33") (pin "4-DIN") (pinfunction "DIN_4-DIN") (pintype "input"))
    )
    (net (code "62") (name "Net-(L33-DOUT)") (class "Default")
      (node (ref "L33") (pin "2-DOUT") (pinfunction "DOUT_2-DOUT") (pintype "output"))
      (node (ref "L34") (pin "4-DIN") (pinfunction "DIN_4-DIN") (pintype "input"))
    )
    (net (code "63") (name "Net-(L34-DOUT)") (class "Default")
      (node (ref "L34") (pin "2-DOUT") (pinfunction "DOUT_2-DOUT") (pintype "output"))
      (node (ref "L35") (pin "4-DIN") (pinfunction "DIN_4-DIN") (pintype "input"))
    )
    (net (code "64") (name "Net-(L35-DOUT)") (class "Default")
      (node (ref "L35") (pin "2-DOUT") (pinfunction "DOUT_2-DOUT") (pintype "output"))
      (node (ref "L36") (pin "4-DIN") (pinfunction "DIN_4-DIN") (pintype "input"))
    )
    (net (code "65") (name "Net-(L36-DOUT)") (class "Default")
      (node (ref "L36") (pin "2-DOUT") (pinfunction "DOUT_2-DOUT") (pintype "output"))
      (node (ref "L37") (pin "4-DIN") (pinfunction "DIN_4-DIN") (pintype "input"))
    )
    (net (code "66") (name "Net-(L37-DOUT)") (class "Default")
      (node (ref "L37") (pin "2-DOUT") (pinfunction "DOUT_2-DOUT") (pintype "output"))
      (node (ref "L38") (pin "4-DIN") (pinfunction "DIN_4-DIN") (pintype "input"))
    )
    (net (code "67") (name "Net-(L38-DOUT)") (class "Default")
      (node (ref "L38") (pin "2-DOUT") (pinfunction "DOUT_2-DOUT") (pintype "output"))
      (node (ref "L39") (pin "4-DIN") (pinfunction "DIN_4-DIN") (pintype "input"))
    )
    (net (code "68") (name "Net-(L39-DOUT)") (class "Default")
      (node (ref "L39") (pin "2-DOUT") (pinfunction "DOUT_2-DOUT") (pintype "output"))
      (node (ref "L40") (pin "4-DIN") (pinfunction "DIN_4-DIN") (pintype "input"))
    )
    (net (code "69") (name "Net-(L40-DOUT)") (class "Default")
      (node (ref "L40") (pin "2-DOUT") (pinfunction "DOUT_2-DOUT") (pintype "output"))
      (node (ref "L41") (pin "4-DIN") (pinfunction "DIN_4-DIN") (pintype "input"))
    )
    (net (code "70") (name "Net-(L41-DOUT)") (class "Default")
      (node (ref "L41") (pin "2-DOUT") (pinfunction "DOUT_2-DOUT") (pintype "output"))
      (node (ref "L42") (pin "4-DIN") (pinfunction "DIN_4-DIN") (pintype "input"))
    )
    (net (code "71") (name "Net-(L42-DOUT)") (class "Default")
      (node (ref "L42") (pin "2-DOUT") (pinfunction "DOUT_2-DOUT") (pintype "output"))
      (node (ref "L43") (pin "4-DIN") (pinfunction "DIN_4-DIN") (pintype "input"))
    )
    (net (code "72") (name "Net-(L43-DOUT)") (class "Default")
      (node (ref "L43") (pin "2-DOUT") (pinfunction "DOUT_2-DOUT") (pintype "output"))
      (node (ref "L44") (pin "4-DIN") (pinfunction "DIN_4-DIN") (pintype "input"))
    )
    (net (code "73") (name "Net-(L44-DOUT)") (class "Default")
      (node (ref "L44") (pin "2-DOUT") (pinfunction "DOUT_2-DOUT") (pintype "output"))
      (node (ref "L45") (pin "4-DIN") (pinfunction "DIN_4-DIN") (pintype "input"))
    )
    (net (code "74") (name "Net-(L45-DOUT)") (class "Default")
      (node (ref "L45") (pin "2-DOUT") (pinfunction "DOUT_2-DOUT") (pintype "output"))
      (node (ref "L46") (pin "4-DIN") (pinfunction "DIN_4-DIN") (pintype "input"))
    )
    (net (code "75") (name "Net-(L46-DOUT)") (class "Default")
      (node (ref "L46") (pin "2-DOUT") (pinfunction "DOUT_2-DOUT") (pintype "output"))
      (node (ref "L47") (pin "4-DIN") (pinfunction "DIN_4-DIN") (pintype "input"))
    )
    (net (code "76") (name "Net-(L47-DOUT)") (class "Default")
      (node (ref "L47") (pin "2-DOUT") (pinfunction "DOUT_2-DOUT") (pintype "output"))
      (node (ref "L48") (pin "4-DIN") (pinfunction "DIN_4-DIN") (pintype "input"))
    )
    (net (code "77") (name "Net-(R6-Pad1)") (class "Default")
      (node (ref "R6") (pin "1") (pinfunction "1_1") (pintype "passive"))
      (node (ref "SJ1") (pin "2") (pinfunction "2_2") (pintype "passive"))
    )
    (net (code "78") (name "Net-(U1-PB6(XTAL1{slash}TOSC1))") (class "Default")
      (node (ref "Q1") (pin "1") (pinfunction "1_1") (pintype "passive"))
      (node (ref "U1") (pin "7") (pinfunction "PB6(XTAL1/TOSC1)_7") (pintype "bidirectional"))
    )
    (net (code "79") (name "Net-(U1-PB7(XTAL2{slash}TOSC2))") (class "Default")
      (node (ref "Q1") (pin "3") (pinfunction "3_3") (pintype "passive"))
      (node (ref "U1") (pin "8") (pinfunction "PB7(XTAL2/TOSC2)_8") (pintype "bidirectional"))
    )
    (net (code "80") (name "RXI") (class "Default")
      (node (ref "JP1") (pin "3") (pinfunction "TXO_3") (pintype "passive"))
      (node (ref "U1") (pin "30") (pinfunction "PD0(RXD)_30") (pintype "bidirectional"))
    )
    (net (code "81") (name "SCK") (class "Default")
      (node (ref "SJ1") (pin "1") (pinfunction "1_1") (pintype "passive"))
      (node (ref "U1") (pin "17") (pinfunction "PB5(SCK)_17") (pintype "bidirectional"))
    )
    (net (code "82") (name "TXO") (class "Default")
      (node (ref "JP1") (pin "2") (pinfunction "RXI_2") (pintype "passive"))
      (node (ref "U1") (pin "31") (pinfunction "PD1(TXD)_31") (pintype "bidirectional"))
    )
    (net (code "83") (name "unconnected-(K1-Pad7)") (class "Default")
      (node (ref "K1") (pin "7") (pinfunction "7_7") (pintype "passive"))
    )
    (net (code "84") (name "unconnected-(K1-Pad10)") (class "Default")
      (node (ref "K1") (pin "10") (pinfunction "10_10") (pintype "passive"))
    )
    (net (code "85") (name "unconnected-(K1-Pad11)") (class "Default")
      (node (ref "K1") (pin "11") (pinfunction "11_11") (pintype "passive"))
    )
    (net (code "86") (name "unconnected-(K1-Pad12)") (class "Default")
      (node (ref "K1") (pin "12") (pinfunction "12_12") (pintype "passive"))
    )
    (net (code "87") (name "unconnected-(K1-Pad13)") (class "Default")
      (node (ref "K1") (pin "13") (pinfunction "13_13") (pintype "passive"))
    )
    (net (code "88") (name "unconnected-(K1-Pad15)") (class "Default")
      (node (ref "K1") (pin "15") (pinfunction "15_15") (pintype "passive"))
    )
    (net (code "89") (name "unconnected-(K1-Pad16)") (class "Default")
      (node (ref "K1") (pin "16") (pinfunction "16_16") (pintype "passive"))
    )
    (net (code "90") (name "unconnected-(K1-Pad18)") (class "Default")
      (node (ref "K1") (pin "18") (pinfunction "18_18") (pintype "passive"))
    )
    (net (code "91") (name "unconnected-(K1-Pad19)") (class "Default")
      (node (ref "K1") (pin "19") (pinfunction "19_19") (pintype "passive"))
    )
    (net (code "92") (name "unconnected-(K1-Pad21)") (class "Default")
      (node (ref "K1") (pin "21") (pinfunction "21_21") (pintype "passive"))
    )
    (net (code "93") (name "unconnected-(K1-Pad22)") (class "Default")
      (node (ref "K1") (pin "22") (pinfunction "22_22") (pintype "passive"))
    )
    (net (code "94") (name "unconnected-(K1-Pad23)") (class "Default")
      (node (ref "K1") (pin "23") (pinfunction "23_23") (pintype "passive"))
    )
    (net (code "95") (name "unconnected-(K1-Pad24)") (class "Default")
      (node (ref "K1") (pin "24") (pinfunction "24_24") (pintype "passive"))
    )
    (net (code "96") (name "unconnected-(K1-Pad26)") (class "Default")
      (node (ref "K1") (pin "26") (pinfunction "26_26") (pintype "passive"))
    )
    (net (code "97") (name "unconnected-(K1-Pad29)") (class "Default")
      (node (ref "K1") (pin "29") (pinfunction "29_29") (pintype "passive"))
    )
    (net (code "98") (name "unconnected-(K1-Pad31)") (class "Default")
      (node (ref "K1") (pin "31") (pinfunction "31_31") (pintype "passive"))
    )
    (net (code "99") (name "unconnected-(K1-Pad32)") (class "Default")
      (node (ref "K1") (pin "32") (pinfunction "32_32") (pintype "passive"))
    )
    (net (code "100") (name "unconnected-(K1-Pad33)") (class "Default")
      (node (ref "K1") (pin "33") (pinfunction "33_33") (pintype "passive"))
    )
    (net (code "101") (name "unconnected-(K1-Pad35)") (class "Default")
      (node (ref "K1") (pin "35") (pinfunction "35_35") (pintype "passive"))
    )
    (net (code "102") (name "unconnected-(K1-Pad36)") (class "Default")
      (node (ref "K1") (pin "36") (pinfunction "36_36") (pintype "passive"))
    )
    (net (code "103") (name "unconnected-(K1-Pad37)") (class "Default")
      (node (ref "K1") (pin "37") (pinfunction "37_37") (pintype "passive"))
    )
    (net (code "104") (name "unconnected-(K1-Pad38)") (class "Default")
      (node (ref "K1") (pin "38") (pinfunction "38_38") (pintype "passive"))
    )
    (net (code "105") (name "unconnected-(K1-Pad40)") (class "Default")
      (node (ref "K1") (pin "40") (pinfunction "40_40") (pintype "passive"))
    )
    (net (code "106") (name "unconnected-(L48-DOUT-Pad2-DOUT)") (class "Default")
      (node (ref "L48") (pin "2-DOUT") (pinfunction "DOUT_2-DOUT") (pintype "output"))
    )
  )
)
